# HYDRA_V3_LINK.net
KiCad netlist of a schematic drawn in Altium Designer
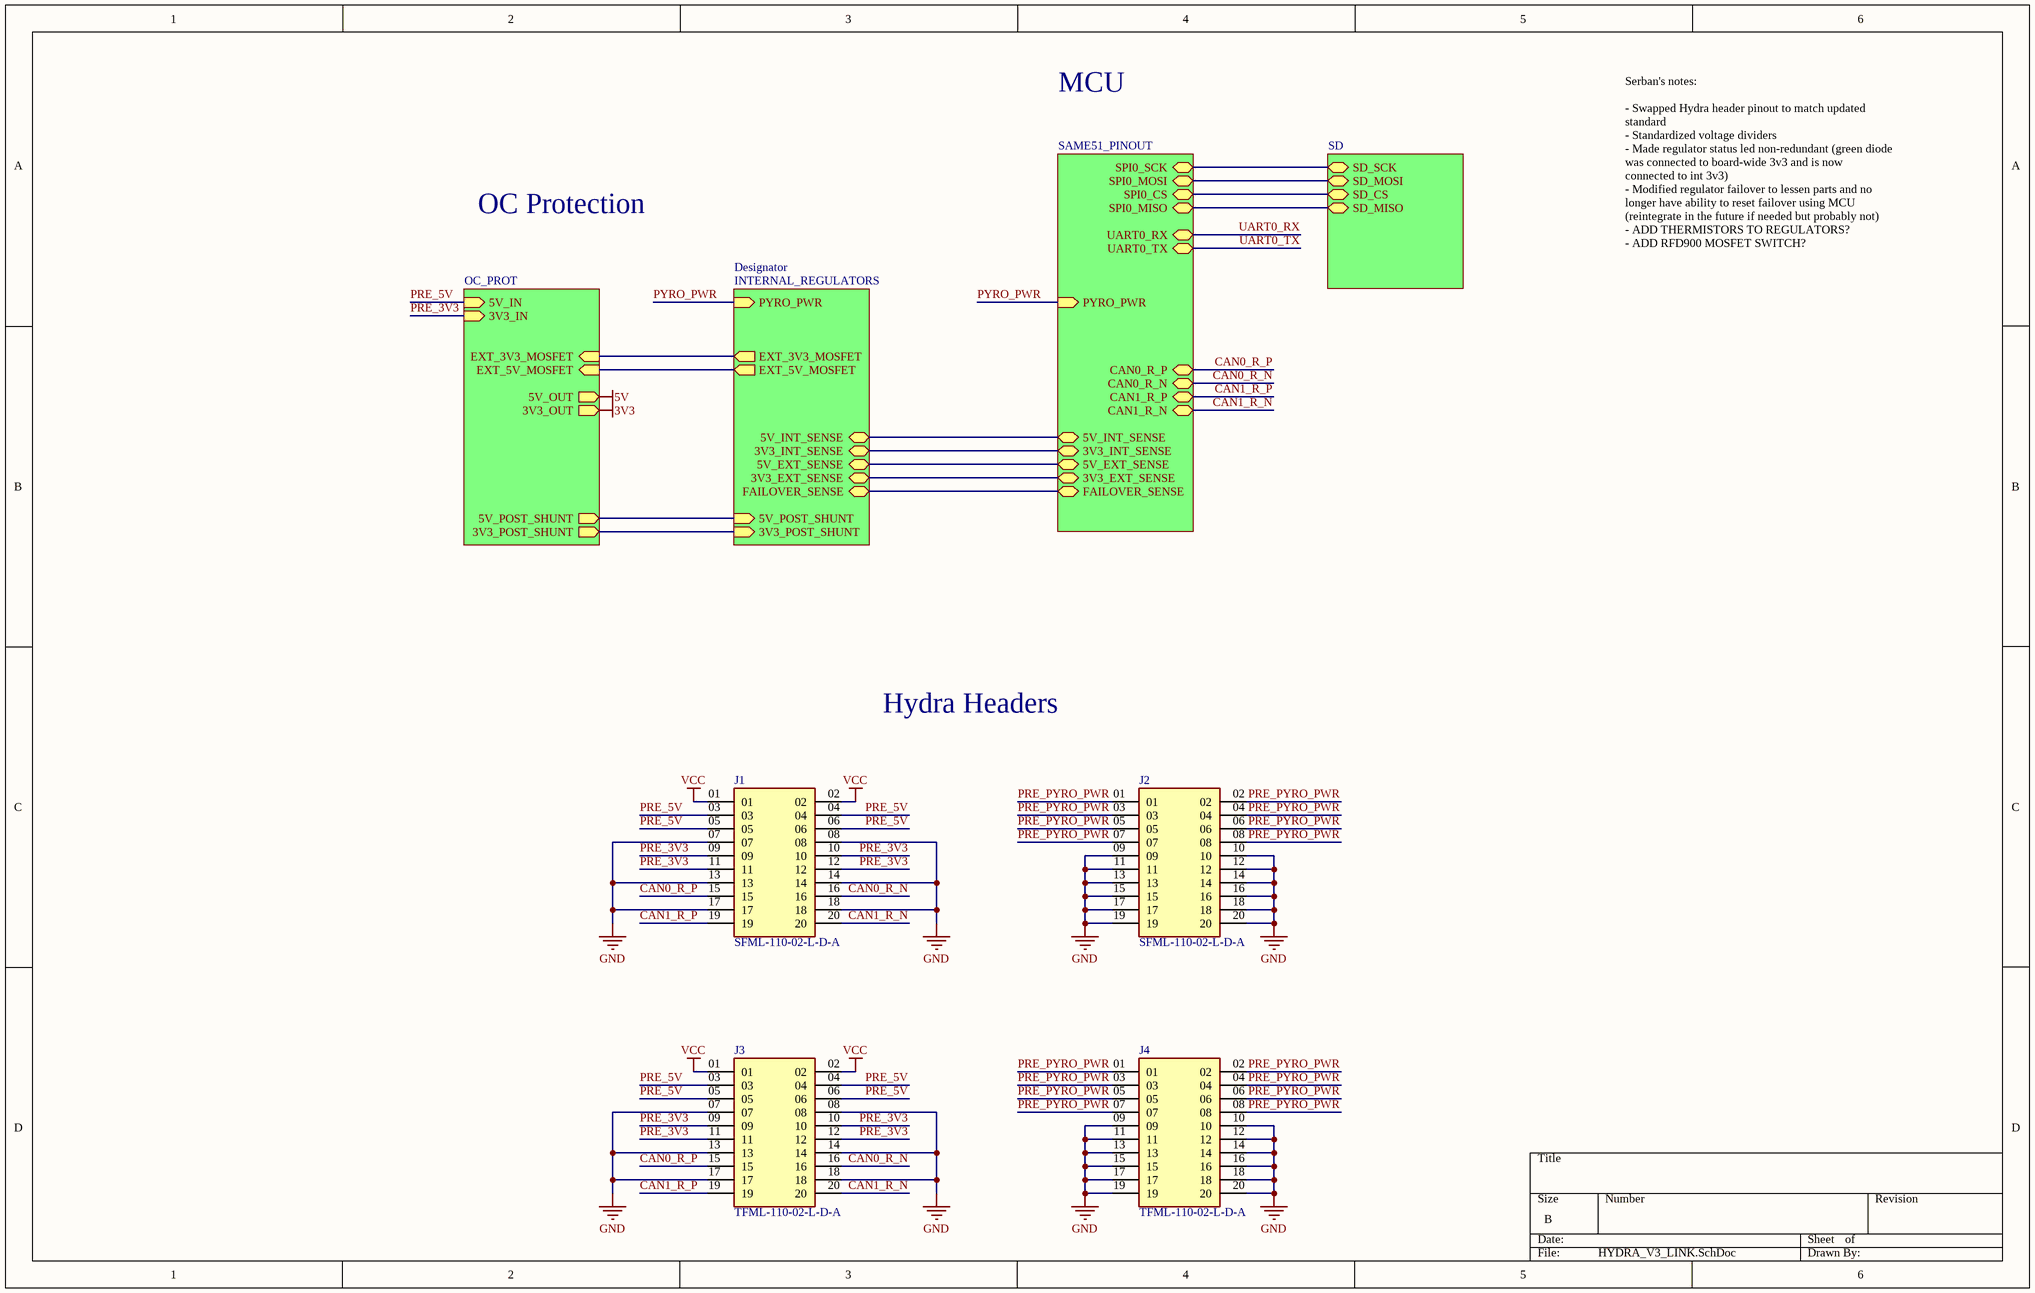
[diagram p0: HYDRA_V3_LINK.SchDoc]

(export (version "E")
  (design (tool "Eeschema 10.0.6"))
  (components
    (comp (ref "J1")
      (value "SFML-110-02-L-D-A")
      (footprint "SFML-110-02-L-D-A-Footprint-1")
      (description "Headers & Wire Housings .050 Tiger Eye High-Reliability Locking Socket Strip")
      (libsource (lib "uORocketry Hardware") (part "SFML-110-02-L-D-A"))
    )
    (comp (ref "J2")
      (value "SFML-110-02-L-D-A")
      (footprint "SFML-110-02-L-D-A-Footprint-1")
      (description "Headers & Wire Housings .050 Tiger Eye High-Reliability Locking Socket Strip")
      (libsource (lib "uORocketry Hardware") (part "SFML-110-02-L-D-A"))
    )
    (comp (ref "J3")
      (value "TFML-110-02-L-D-A")
      (footprint "TFML-110-02-L-D-A-Footprint-1")
      (description "Conn Shrouded Header (4 Sides) HDR 20 POS 1.27mm Solder ST Top Entry SMD TIGER EYE™ Tube")
      (libsource (lib "uORocketry Hardware") (part "TFML-110-02-L-D-A"))
    )
    (comp (ref "J4")
      (value "TFML-110-02-L-D-A")
      (footprint "TFML-110-02-L-D-A-Footprint-1")
      (description "Conn Shrouded Header (4 Sides) HDR 20 POS 1.27mm Solder ST Top Entry SMD TIGER EYE™ Tube")
      (libsource (lib "uORocketry Hardware") (part "TFML-110-02-L-D-A"))
    )
  )
  (nets
    (net (code "7") (name "/CAN0_R_N") (class "Default")
      (node (ref "J1") (pin "16") (pinfunction "16_16") (pintype "passive"))
      (node (ref "J3") (pin "16") (pinfunction "16_16") (pintype "passive"))
    )
    (net (code "8") (name "/CAN0_R_P") (class "Default")
      (node (ref "J1") (pin "15") (pinfunction "15_15") (pintype "passive"))
      (node (ref "J3") (pin "15") (pinfunction "15_15") (pintype "passive"))
    )
    (net (code "9") (name "/CAN1_R_N") (class "Default")
      (node (ref "J1") (pin "20") (pinfunction "20_20") (pintype "passive"))
      (node (ref "J3") (pin "20") (pinfunction "20_20") (pintype "passive"))
    )
    (net (code "10") (name "/CAN1_R_P") (class "Default")
      (node (ref "J1") (pin "19") (pinfunction "19_19") (pintype "passive"))
      (node (ref "J3") (pin "19") (pinfunction "19_19") (pintype "passive"))
    )
    (net (code "14") (name "/PRE_3V3") (class "Default")
      (node (ref "J1") (pin "09") (pinfunction "09_09") (pintype "passive"))
      (node (ref "J1") (pin "10") (pinfunction "10_10") (pintype "passive"))
      (node (ref "J1") (pin "11") (pinfunction "11_11") (pintype "passive"))
      (node (ref "J1") (pin "12") (pinfunction "12_12") (pintype "passive"))
      (node (ref "J3") (pin "09") (pinfunction "09_09") (pintype "passive"))
      (node (ref "J3") (pin "10") (pinfunction "10_10") (pintype "passive"))
      (node (ref "J3") (pin "11") (pinfunction "11_11") (pintype "passive"))
      (node (ref "J3") (pin "12") (pinfunction "12_12") (pintype "passive"))
    )
    (net (code "15") (name "/PRE_5V") (class "Default")
      (node (ref "J1") (pin "03") (pinfunction "03_03") (pintype "passive"))
      (node (ref "J1") (pin "04") (pinfunction "04_04") (pintype "passive"))
      (node (ref "J1") (pin "05") (pinfunction "05_05") (pintype "passive"))
      (node (ref "J1") (pin "06") (pinfunction "06_06") (pintype "passive"))
      (node (ref "J3") (pin "03") (pinfunction "03_03") (pintype "passive"))
      (node (ref "J3") (pin "04") (pinfunction "04_04") (pintype "passive"))
      (node (ref "J3") (pin "05") (pinfunction "05_05") (pintype "passive"))
      (node (ref "J3") (pin "06") (pinfunction "06_06") (pintype "passive"))
    )
    (net (code "16") (name "/PRE_PYRO_PWR") (class "Default")
      (node (ref "J2") (pin "01") (pinfunction "01_01") (pintype "passive"))
      (node (ref "J2") (pin "02") (pinfunction "02_02") (pintype "passive"))
      (node (ref "J2") (pin "03") (pinfunction "03_03") (pintype "passive"))
      (node (ref "J2") (pin "04") (pinfunction "04_04") (pintype "passive"))
      (node (ref "J2") (pin "05") (pinfunction "05_05") (pintype "passive"))
      (node (ref "J2") (pin "06") (pinfunction "06_06") (pintype "passive"))
      (node (ref "J2") (pin "07") (pinfunction "07_07") (pintype "passive"))
      (node (ref "J2") (pin "08") (pinfunction "08_08") (pintype "passive"))
      (node (ref "J4") (pin "01") (pinfunction "01_01") (pintype "passive"))
      (node (ref "J4") (pin "02") (pinfunction "02_02") (pintype "passive"))
      (node (ref "J4") (pin "03") (pinfunction "03_03") (pintype "passive"))
      (node (ref "J4") (pin "04") (pinfunction "04_04") (pintype "passive"))
      (node (ref "J4") (pin "05") (pinfunction "05_05") (pintype "passive"))
      (node (ref "J4") (pin "06") (pinfunction "06_06") (pintype "passive"))
      (node (ref "J4") (pin "07") (pinfunction "07_07") (pintype "passive"))
      (node (ref "J4") (pin "08") (pinfunction "08_08") (pintype "passive"))
    )
    (net (code "26") (name "GND") (class "Default")
      (node (ref "J1") (pin "07") (pinfunction "07_07") (pintype "passive"))
      (node (ref "J1") (pin "08") (pinfunction "08_08") (pintype "passive"))
      (node (ref "J1") (pin "13") (pinfunction "13_13") (pintype "passive"))
      (node (ref "J1") (pin "14") (pinfunction "14_14") (pintype "passive"))
      (node (ref "J1") (pin "17") (pinfunction "17_17") (pintype "passive"))
      (node (ref "J1") (pin "18") (pinfunction "18_18") (pintype "passive"))
      (node (ref "J2") (pin "09") (pinfunction "09_09") (pintype "passive"))
      (node (ref "J2") (pin "10") (pinfunction "10_10") (pintype "passive"))
      (node (ref "J2") (pin "11") (pinfunction "11_11") (pintype "passive"))
      (node (ref "J2") (pin "12") (pinfunction "12_12") (pintype "passive"))
      (node (ref "J2") (pin "13") (pinfunction "13_13") (pintype "passive"))
      (node (ref "J2") (pin "14") (pinfunction "14_14") (pintype "passive"))
      (node (ref "J2") (pin "15") (pinfunction "15_15") (pintype "passive"))
      (node (ref "J2") (pin "16") (pinfunction "16_16") (pintype "passive"))
      (node (ref "J2") (pin "17") (pinfunction "17_17") (pintype "passive"))
      (node (ref "J2") (pin "18") (pinfunction "18_18") (pintype "passive"))
      (node (ref "J2") (pin "19") (pinfunction "19_19") (pintype "passive"))
      (node (ref "J2") (pin "20") (pinfunction "20_20") (pintype "passive"))
      (node (ref "J3") (pin "07") (pinfunction "07_07") (pintype "passive"))
      (node (ref "J3") (pin "08") (pinfunction "08_08") (pintype "passive"))
      (node (ref "J3") (pin "13") (pinfunction "13_13") (pintype "passive"))
      (node (ref "J3") (pin "14") (pinfunction "14_14") (pintype "passive"))
      (node (ref "J3") (pin "17") (pinfunction "17_17") (pintype "passive"))
      (node (ref "J3") (pin "18") (pinfunction "18_18") (pintype "passive"))
      (node (ref "J4") (pin "09") (pinfunction "09_09") (pintype "passive"))
      (node (ref "J4") (pin "10") (pinfunction "10_10") (pintype "passive"))
      (node (ref "J4") (pin "11") (pinfunction "11_11") (pintype "passive"))
      (node (ref "J4") (pin "12") (pinfunction "12_12") (pintype "passive"))
      (node (ref "J4") (pin "13") (pinfunction "13_13") (pintype "passive"))
      (node (ref "J4") (pin "14") (pinfunction "14_14") (pintype "passive"))
      (node (ref "J4") (pin "15") (pinfunction "15_15") (pintype "passive"))
      (node (ref "J4") (pin "16") (pinfunction "16_16") (pintype "passive"))
      (node (ref "J4") (pin "17") (pinfunction "17_17") (pintype "passive"))
      (node (ref "J4") (pin "18") (pinfunction "18_18") (pintype "passive"))
      (node (ref "J4") (pin "19") (pinfunction "19_19") (pintype "passive"))
      (node (ref "J4") (pin "20") (pinfunction "20_20") (pintype "passive"))
    )
    (net (code "27") (name "VCC") (class "Default")
      (node (ref "J1") (pin "01") (pinfunction "01_01") (pintype "passive"))
      (node (ref "J1") (pin "02") (pinfunction "02_02") (pintype "passive"))
      (node (ref "J3") (pin "01") (pinfunction "01_01") (pintype "passive"))
      (node (ref "J3") (pin "02") (pinfunction "02_02") (pintype "passive"))
    )
  )
)
